# ActiveHeadphoneBreadboard.net
KiCad netlist of a schematic drawn in EAGLE
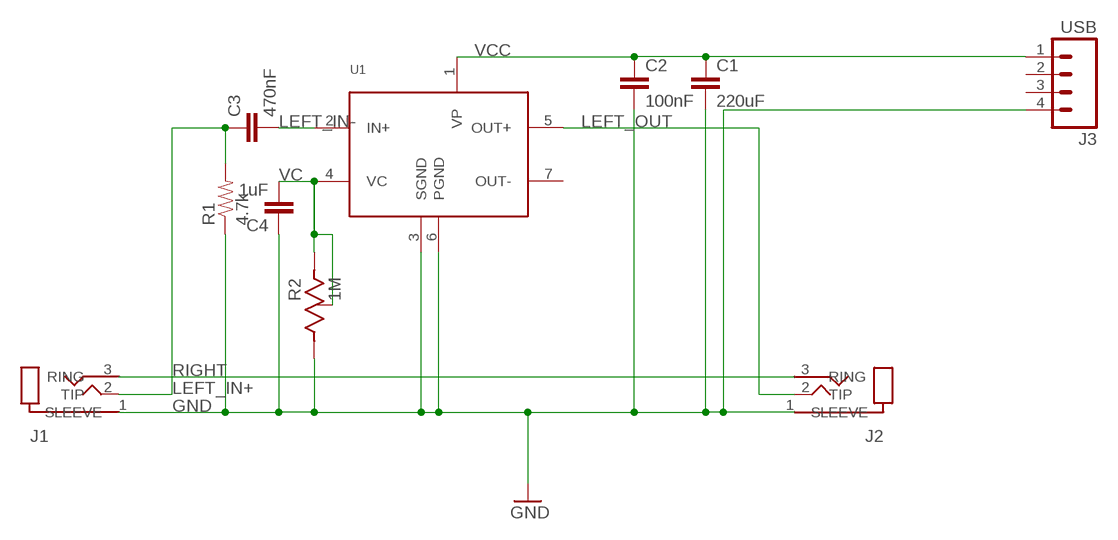
[diagram p0: schematic, sheet 1]

(export (version "E")
  (design (tool "Eeschema 10.0.6"))
  (components
    (comp (ref "C1")
      (value "220uF")
      (footprint "eagle-import:CAP-PTH-5MM")
      (libsource (lib "eagle-import") (part "CAPPTH1"))
    )
    (comp (ref "C2")
      (value "100nF")
      (footprint "eagle-import:CAP-PTH-5MM")
      (libsource (lib "eagle-import") (part "CAPPTH1"))
    )
    (comp (ref "C3")
      (value "470nF")
      (footprint "eagle-import:CAP-PTH-SMALL")
      (libsource (lib "eagle-import") (part "CAPPTH"))
    )
    (comp (ref "C4")
      (value "1uF")
      (footprint "eagle-import:CAP-PTH-SMALL")
      (libsource (lib "eagle-import") (part "CAPPTH"))
    )
    (comp (ref "J1")
      (value "SJ1-35XXPTH")
      (footprint "eagle-import:SJ1-3523N")
      (libsource (lib "eagle-import") (part "SJ1-35XXPTH"))
    )
    (comp (ref "J2")
      (value "SJ1-35XXPTH")
      (footprint "eagle-import:SJ1-3523N")
      (libsource (lib "eagle-import") (part "SJ1-35XXPTH"))
    )
    (comp (ref "J3")
      (value "USB")
      (footprint "eagle-import:1X04")
      (libsource (lib "eagle-import") (part "M04PTH"))
    )
    (comp (ref "R1")
      (value "4.7k")
      (footprint "eagle-import:AXIAL-0.4")
      (libsource (lib "eagle-import") (part "RESISTORPTH-1/4W"))
    )
    (comp (ref "R2")
      (value "1M")
      (footprint "eagle-import:3352T")
      (libsource (lib "eagle-import") (part "3352T"))
    )
    (comp (ref "U1")
      (value "TDA7052")
      (footprint "eagle-import:DIL-8")
      (libsource (lib "eagle-import") (part "TDA7052"))
    )
  )
  (nets
    (net (code "1") (name "/LEFT_IN+") (class "Default")
      (node (ref "C3") (pin "1") (pinfunction "1_1") (pintype "passive"))
      (node (ref "J1") (pin "2") (pinfunction "TIP_2") (pintype "bidirectional"))
      (node (ref "R1") (pin "P$2") (pinfunction "2_P$2") (pintype "passive"))
    )
    (net (code "2") (name "/LEFT_IN-") (class "Default")
      (node (ref "C3") (pin "2") (pinfunction "2_2") (pintype "passive"))
      (node (ref "U1") (pin "2") (pinfunction "IN+_2") (pintype "bidirectional"))
    )
    (net (code "3") (name "/LEFT_OUT") (class "Default")
      (node (ref "J2") (pin "2") (pinfunction "TIP_2") (pintype "bidirectional"))
      (node (ref "U1") (pin "5") (pinfunction "OUT+_5") (pintype "bidirectional"))
    )
    (net (code "4") (name "/RIGHT") (class "Default")
      (node (ref "J1") (pin "3") (pinfunction "RING_3") (pintype "bidirectional"))
      (node (ref "J2") (pin "3") (pinfunction "RING_3") (pintype "bidirectional"))
    )
    (net (code "5") (name "/VC") (class "Default")
      (node (ref "C4") (pin "2") (pinfunction "2_2") (pintype "passive"))
      (node (ref "R2") (pin "2") (pinfunction "WIPER_2") (pintype "bidirectional"))
      (node (ref "R2") (pin "3") (pinfunction "CW_3") (pintype "bidirectional"))
      (node (ref "U1") (pin "4") (pinfunction "VC_4") (pintype "bidirectional"))
    )
    (net (code "6") (name "/VCC") (class "Default")
      (node (ref "C1") (pin "1") (pinfunction "1_1") (pintype "passive"))
      (node (ref "C2") (pin "1") (pinfunction "1_1") (pintype "passive"))
      (node (ref "J3") (pin "1") (pinfunction "1_1") (pintype "passive"))
      (node (ref "U1") (pin "1") (pinfunction "VP_1") (pintype "bidirectional"))
    )
    (net (code "7") (name "GND") (class "Default")
      (node (ref "C1") (pin "2") (pinfunction "2_2") (pintype "passive"))
      (node (ref "C2") (pin "2") (pinfunction "2_2") (pintype "passive"))
      (node (ref "C4") (pin "1") (pinfunction "1_1") (pintype "passive"))
      (node (ref "J1") (pin "1") (pinfunction "SLEEVE_1") (pintype "bidirectional"))
      (node (ref "J2") (pin "1") (pinfunction "SLEEVE_1") (pintype "bidirectional"))
      (node (ref "J3") (pin "4") (pinfunction "4_4") (pintype "passive"))
      (node (ref "R1") (pin "P$1") (pinfunction "1_P$1") (pintype "passive"))
      (node (ref "R2") (pin "1") (pinfunction "CCW_1") (pintype "bidirectional"))
      (node (ref "U1") (pin "3") (pinfunction "SGND_3") (pintype "bidirectional"))
      (node (ref "U1") (pin "6") (pinfunction "PGND_6") (pintype "bidirectional"))
    )
    (net (code "8") (name "unconnected-(J3-Pad2)") (class "Default")
      (node (ref "J3") (pin "2") (pinfunction "2_2") (pintype "passive"))
    )
    (net (code "9") (name "unconnected-(J3-Pad3)") (class "Default")
      (node (ref "J3") (pin "3") (pinfunction "3_3") (pintype "passive"))
    )
    (net (code "10") (name "unconnected-(U1-OUT--Pad7)") (class "Default")
      (node (ref "U1") (pin "7") (pinfunction "OUT-_7") (pintype "bidirectional"))
    )
  )
)
